# Atari_2600_PP.net
KiCad netlist of a schematic drawn in EAGLE
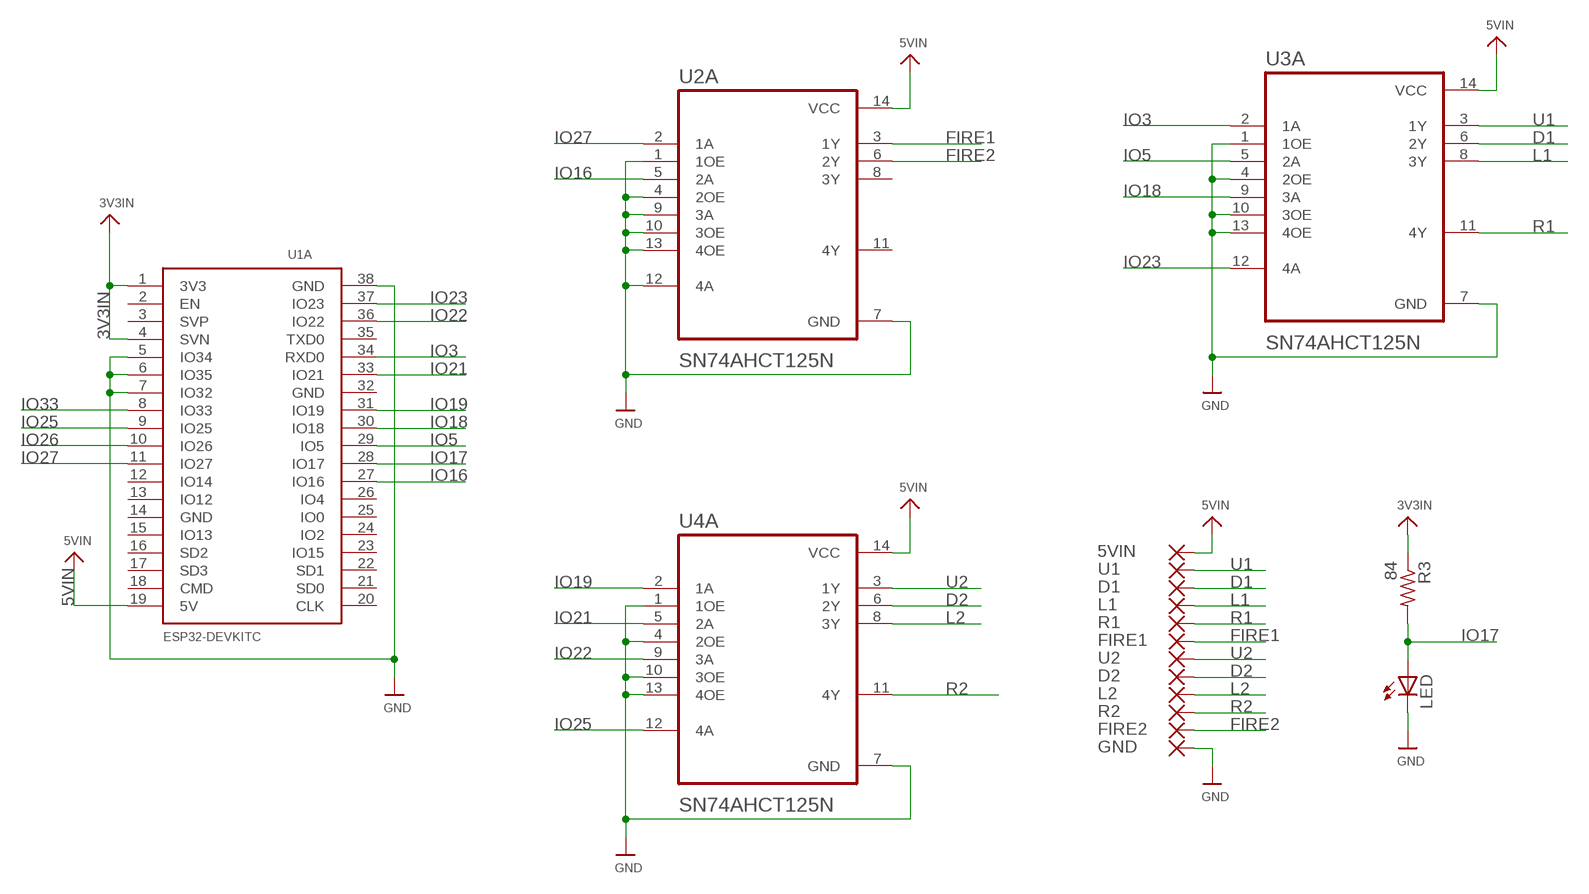
[diagram p0: schematic, sheet 1]

(export (version "E")
  (design (tool "Eeschema 10.0.6"))
  (components
    (comp (ref "5VIN")
      (value "SMD5")
      (footprint "eagle-import:SMD2,54-5,08")
      (libsource (lib "eagle-import") (part "SMD5"))
    )
    (comp (ref "D1")
      (value "SMD5")
      (footprint "eagle-import:SMD2,54-5,08")
      (libsource (lib "eagle-import") (part "SMD5"))
    )
    (comp (ref "D2")
      (value "SMD5")
      (footprint "eagle-import:SMD2,54-5,08")
      (libsource (lib "eagle-import") (part "SMD5"))
    )
    (comp (ref "FIRE1")
      (value "SMD5")
      (footprint "eagle-import:SMD2,54-5,08")
      (libsource (lib "eagle-import") (part "SMD5"))
    )
    (comp (ref "FIRE2")
      (value "SMD5")
      (footprint "eagle-import:SMD2,54-5,08")
      (libsource (lib "eagle-import") (part "SMD5"))
    )
    (comp (ref "GND")
      (value "SMD5")
      (footprint "eagle-import:SMD2,54-5,08")
      (libsource (lib "eagle-import") (part "SMD5"))
    )
    (comp (ref "L1")
      (value "SMD5")
      (footprint "eagle-import:SMD2,54-5,08")
      (libsource (lib "eagle-import") (part "SMD5"))
    )
    (comp (ref "L2")
      (value "SMD5")
      (footprint "eagle-import:SMD2,54-5,08")
      (libsource (lib "eagle-import") (part "SMD5"))
    )
    (comp (ref "LED")
      (value "LEDCHIPLED_1206")
      (footprint "eagle-import:CHIPLED_1206")
      (libsource (lib "eagle-import") (part "LEDCHIPLED_1206"))
    )
    (comp (ref "R1")
      (value "SMD5")
      (footprint "eagle-import:SMD2,54-5,08")
      (libsource (lib "eagle-import") (part "SMD5"))
    )
    (comp (ref "R2")
      (value "SMD5")
      (footprint "eagle-import:SMD2,54-5,08")
      (libsource (lib "eagle-import") (part "SMD5"))
    )
    (comp (ref "R3")
      (value "84")
      (footprint "eagle-import:R1206")
      (libsource (lib "eagle-import") (part "R-US_R1206"))
    )
    (comp (ref "U1")
      (value "SMD5")
      (footprint "eagle-import:SMD2,54-5,08")
      (libsource (lib "eagle-import") (part "SMD5"))
    )
    (comp (ref "U1A")
      (value "ESP32DEVKITC")
      (footprint "eagle-import:ESP32-DEVKITC")
      (libsource (lib "eagle-import") (part "ESP32DEVKITC"))
    )
    (comp (ref "U2")
      (value "SMD5")
      (footprint "eagle-import:SMD2,54-5,08")
      (libsource (lib "eagle-import") (part "SMD5"))
    )
    (comp (ref "U2A")
      (value "SN74AHCT125N")
      (footprint "eagle-import:DIP794W45P254L1969H508Q14")
      (fields (field (name "MF") "Texas Instruments"))
      (libsource (lib "eagle-import") (part "SN74AHCT125N"))
    )
    (comp (ref "U3A")
      (value "SN74AHCT125N")
      (footprint "eagle-import:DIP794W45P254L1969H508Q14")
      (fields (field (name "MF") "Texas Instruments"))
      (libsource (lib "eagle-import") (part "SN74AHCT125N"))
    )
    (comp (ref "U4A")
      (value "SN74AHCT125N")
      (footprint "eagle-import:DIP794W45P254L1969H508Q14")
      (fields (field (name "MF") "Texas Instruments"))
      (libsource (lib "eagle-import") (part "SN74AHCT125N"))
    )
  )
  (nets
    (net (code "1") (name "/D1") (class "Default")
      (node (ref "D1") (pin "1") (pinfunction "P_1") (pintype "passive"))
      (node (ref "U3A") (pin "6") (pinfunction "2Y_6") (pintype "output"))
    )
    (net (code "2") (name "/D2") (class "Default")
      (node (ref "D2") (pin "1") (pinfunction "P_1") (pintype "passive"))
      (node (ref "U4A") (pin "6") (pinfunction "2Y_6") (pintype "output"))
    )
    (net (code "3") (name "/FIRE1") (class "Default")
      (node (ref "FIRE1") (pin "1") (pinfunction "P_1") (pintype "passive"))
      (node (ref "U2A") (pin "3") (pinfunction "1Y_3") (pintype "output"))
    )
    (net (code "4") (name "/FIRE2") (class "Default")
      (node (ref "FIRE2") (pin "1") (pinfunction "P_1") (pintype "passive"))
      (node (ref "U2A") (pin "6") (pinfunction "2Y_6") (pintype "output"))
    )
    (net (code "5") (name "/IO3") (class "Default")
      (node (ref "U1A") (pin "34") (pinfunction "RXD0_34") (pintype "bidirectional"))
      (node (ref "U3A") (pin "2") (pinfunction "1A_2") (pintype "input"))
    )
    (net (code "6") (name "/IO5") (class "Default")
      (node (ref "U1A") (pin "29") (pinfunction "IO5_29") (pintype "bidirectional"))
      (node (ref "U3A") (pin "5") (pinfunction "2A_5") (pintype "input"))
    )
    (net (code "7") (name "/IO16") (class "Default")
      (node (ref "U1A") (pin "27") (pinfunction "IO16_27") (pintype "bidirectional"))
      (node (ref "U2A") (pin "5") (pinfunction "2A_5") (pintype "input"))
    )
    (net (code "8") (name "/IO17") (class "Default")
      (node (ref "LED") (pin "A") (pinfunction "A_A") (pintype "passive"))
      (node (ref "R3") (pin "2") (pinfunction "2_2") (pintype "passive"))
      (node (ref "U1A") (pin "28") (pinfunction "IO17_28") (pintype "bidirectional"))
    )
    (net (code "9") (name "/IO18") (class "Default")
      (node (ref "U1A") (pin "30") (pinfunction "IO18_30") (pintype "bidirectional"))
      (node (ref "U3A") (pin "9") (pinfunction "3A_9") (pintype "input"))
    )
    (net (code "10") (name "/IO19") (class "Default")
      (node (ref "U1A") (pin "31") (pinfunction "IO19_31") (pintype "bidirectional"))
      (node (ref "U4A") (pin "2") (pinfunction "1A_2") (pintype "input"))
    )
    (net (code "11") (name "/IO21") (class "Default")
      (node (ref "U1A") (pin "33") (pinfunction "IO21_33") (pintype "bidirectional"))
      (node (ref "U4A") (pin "5") (pinfunction "2A_5") (pintype "input"))
    )
    (net (code "12") (name "/IO22") (class "Default")
      (node (ref "U1A") (pin "36") (pinfunction "IO22_36") (pintype "bidirectional"))
      (node (ref "U4A") (pin "9") (pinfunction "3A_9") (pintype "input"))
    )
    (net (code "13") (name "/IO23") (class "Default")
      (node (ref "U1A") (pin "37") (pinfunction "IO23_37") (pintype "bidirectional"))
      (node (ref "U3A") (pin "12") (pinfunction "4A_12") (pintype "bidirectional"))
    )
    (net (code "14") (name "/IO25") (class "Default")
      (node (ref "U1A") (pin "9") (pinfunction "IO25_9") (pintype "bidirectional"))
      (node (ref "U4A") (pin "12") (pinfunction "4A_12") (pintype "bidirectional"))
    )
    (net (code "15") (name "/IO26") (class "Default")
      (node (ref "U1A") (pin "10") (pinfunction "IO26_10") (pintype "bidirectional"))
    )
    (net (code "16") (name "/IO27") (class "Default")
      (node (ref "U1A") (pin "11") (pinfunction "IO27_11") (pintype "bidirectional"))
      (node (ref "U2A") (pin "2") (pinfunction "1A_2") (pintype "input"))
    )
    (net (code "17") (name "/IO33") (class "Default")
      (node (ref "U1A") (pin "8") (pinfunction "IO33_8") (pintype "bidirectional"))
    )
    (net (code "18") (name "/L1") (class "Default")
      (node (ref "L1") (pin "1") (pinfunction "P_1") (pintype "passive"))
      (node (ref "U3A") (pin "8") (pinfunction "3Y_8") (pintype "output"))
    )
    (net (code "19") (name "/L2") (class "Default")
      (node (ref "L2") (pin "1") (pinfunction "P_1") (pintype "passive"))
      (node (ref "U4A") (pin "8") (pinfunction "3Y_8") (pintype "output"))
    )
    (net (code "20") (name "/R1") (class "Default")
      (node (ref "R1") (pin "1") (pinfunction "P_1") (pintype "passive"))
      (node (ref "U3A") (pin "11") (pinfunction "4Y_11") (pintype "output"))
    )
    (net (code "21") (name "/R2") (class "Default")
      (node (ref "R2") (pin "1") (pinfunction "P_1") (pintype "passive"))
      (node (ref "U4A") (pin "11") (pinfunction "4Y_11") (pintype "output"))
    )
    (net (code "22") (name "/U1") (class "Default")
      (node (ref "U1") (pin "1") (pinfunction "P_1") (pintype "passive"))
      (node (ref "U3A") (pin "3") (pinfunction "1Y_3") (pintype "output"))
    )
    (net (code "23") (name "/U2") (class "Default")
      (node (ref "U2") (pin "1") (pinfunction "P_1") (pintype "passive"))
      (node (ref "U4A") (pin "3") (pinfunction "1Y_3") (pintype "output"))
    )
    (net (code "24") (name "3V3IN") (class "Default")
      (node (ref "R3") (pin "1") (pinfunction "1_1") (pintype "passive"))
      (node (ref "U1A") (pin "1") (pinfunction "3V3_1") (pintype "bidirectional"))
      (node (ref "U1A") (pin "4") (pinfunction "SVN_4") (pintype "bidirectional"))
    )
    (net (code "25") (name "5VIN") (class "Default")
      (node (ref "5VIN") (pin "1") (pinfunction "P_1") (pintype "passive"))
      (node (ref "U1A") (pin "19") (pinfunction "5V_19") (pintype "bidirectional"))
      (node (ref "U2A") (pin "14") (pinfunction "VCC_14") (pintype "power_in"))
      (node (ref "U3A") (pin "14") (pinfunction "VCC_14") (pintype "power_in"))
      (node (ref "U4A") (pin "14") (pinfunction "VCC_14") (pintype "power_in"))
    )
    (net (code "26") (name "GND") (class "Default")
      (node (ref "GND") (pin "1") (pinfunction "P_1") (pintype "passive"))
      (node (ref "LED") (pin "C") (pinfunction "C_C") (pintype "passive"))
      (node (ref "U1A") (pin "38") (pinfunction "GND_38") (pintype "bidirectional"))
      (node (ref "U1A") (pin "5") (pinfunction "IO34_5") (pintype "bidirectional"))
      (node (ref "U1A") (pin "6") (pinfunction "IO35_6") (pintype "bidirectional"))
      (node (ref "U1A") (pin "7") (pinfunction "IO32_7") (pintype "bidirectional"))
      (node (ref "U2A") (pin "1") (pinfunction "1OE_1") (pintype "input"))
      (node (ref "U2A") (pin "10") (pinfunction "3OE_10") (pintype "input"))
      (node (ref "U2A") (pin "12") (pinfunction "4A_12") (pintype "bidirectional"))
      (node (ref "U2A") (pin "13") (pinfunction "4OE_13") (pintype "input"))
      (node (ref "U2A") (pin "4") (pinfunction "2OE_4") (pintype "input"))
      (node (ref "U2A") (pin "7") (pinfunction "GND_7") (pintype "power_in"))
      (node (ref "U2A") (pin "9") (pinfunction "3A_9") (pintype "input"))
      (node (ref "U3A") (pin "1") (pinfunction "1OE_1") (pintype "input"))
      (node (ref "U3A") (pin "10") (pinfunction "3OE_10") (pintype "input"))
      (node (ref "U3A") (pin "13") (pinfunction "4OE_13") (pintype "input"))
      (node (ref "U3A") (pin "4") (pinfunction "2OE_4") (pintype "input"))
      (node (ref "U3A") (pin "7") (pinfunction "GND_7") (pintype "power_in"))
      (node (ref "U4A") (pin "1") (pinfunction "1OE_1") (pintype "input"))
      (node (ref "U4A") (pin "10") (pinfunction "3OE_10") (pintype "input"))
      (node (ref "U4A") (pin "13") (pinfunction "4OE_13") (pintype "input"))
      (node (ref "U4A") (pin "4") (pinfunction "2OE_4") (pintype "input"))
      (node (ref "U4A") (pin "7") (pinfunction "GND_7") (pintype "power_in"))
    )
    (net (code "27") (name "unconnected-(U1A-CLK-Pad20)") (class "Default")
      (node (ref "U1A") (pin "20") (pinfunction "CLK_20") (pintype "bidirectional"))
    )
    (net (code "28") (name "unconnected-(U1A-CMD-Pad18)") (class "Default")
      (node (ref "U1A") (pin "18") (pinfunction "CMD_18") (pintype "bidirectional"))
    )
    (net (code "29") (name "unconnected-(U1A-EN-Pad2)") (class "Default")
      (node (ref "U1A") (pin "2") (pinfunction "EN_2") (pintype "bidirectional"))
    )
    (net (code "30") (name "unconnected-(U1A-GND-Pad14)") (class "Default")
      (node (ref "U1A") (pin "14") (pinfunction "GND_14") (pintype "bidirectional"))
    )
    (net (code "31") (name "unconnected-(U1A-GND-Pad32)") (class "Default")
      (node (ref "U1A") (pin "32") (pinfunction "GND_32") (pintype "bidirectional"))
    )
    (net (code "32") (name "unconnected-(U1A-IO0-Pad25)") (class "Default")
      (node (ref "U1A") (pin "25") (pinfunction "IO0_25") (pintype "bidirectional"))
    )
    (net (code "33") (name "unconnected-(U1A-IO2-Pad24)") (class "Default")
      (node (ref "U1A") (pin "24") (pinfunction "IO2_24") (pintype "bidirectional"))
    )
    (net (code "34") (name "unconnected-(U1A-IO4-Pad26)") (class "Default")
      (node (ref "U1A") (pin "26") (pinfunction "IO4_26") (pintype "bidirectional"))
    )
    (net (code "35") (name "unconnected-(U1A-IO12-Pad13)") (class "Default")
      (node (ref "U1A") (pin "13") (pinfunction "IO12_13") (pintype "bidirectional"))
    )
    (net (code "36") (name "unconnected-(U1A-IO13-Pad15)") (class "Default")
      (node (ref "U1A") (pin "15") (pinfunction "IO13_15") (pintype "bidirectional"))
    )
    (net (code "37") (name "unconnected-(U1A-IO14-Pad12)") (class "Default")
      (node (ref "U1A") (pin "12") (pinfunction "IO14_12") (pintype "bidirectional"))
    )
    (net (code "38") (name "unconnected-(U1A-IO15-Pad23)") (class "Default")
      (node (ref "U1A") (pin "23") (pinfunction "IO15_23") (pintype "bidirectional"))
    )
    (net (code "39") (name "unconnected-(U1A-SD0-Pad21)") (class "Default")
      (node (ref "U1A") (pin "21") (pinfunction "SD0_21") (pintype "bidirectional"))
    )
    (net (code "40") (name "unconnected-(U1A-SD1-Pad22)") (class "Default")
      (node (ref "U1A") (pin "22") (pinfunction "SD1_22") (pintype "bidirectional"))
    )
    (net (code "41") (name "unconnected-(U1A-SD2-Pad16)") (class "Default")
      (node (ref "U1A") (pin "16") (pinfunction "SD2_16") (pintype "bidirectional"))
    )
    (net (code "42") (name "unconnected-(U1A-SD3-Pad17)") (class "Default")
      (node (ref "U1A") (pin "17") (pinfunction "SD3_17") (pintype "bidirectional"))
    )
    (net (code "43") (name "unconnected-(U1A-SVP-Pad3)") (class "Default")
      (node (ref "U1A") (pin "3") (pinfunction "SVP_3") (pintype "bidirectional"))
    )
    (net (code "44") (name "unconnected-(U1A-TXD0-Pad35)") (class "Default")
      (node (ref "U1A") (pin "35") (pinfunction "TXD0_35") (pintype "bidirectional"))
    )
    (net (code "45") (name "unconnected-(U2A-3Y-Pad8)") (class "Default")
      (node (ref "U2A") (pin "8") (pinfunction "3Y_8") (pintype "output"))
    )
    (net (code "46") (name "unconnected-(U2A-4Y-Pad11)") (class "Default")
      (node (ref "U2A") (pin "11") (pinfunction "4Y_11") (pintype "output"))
    )
  )
)
